# mcu_subsystem.net
KiCad netlist of a schematic drawn in Altium Designer
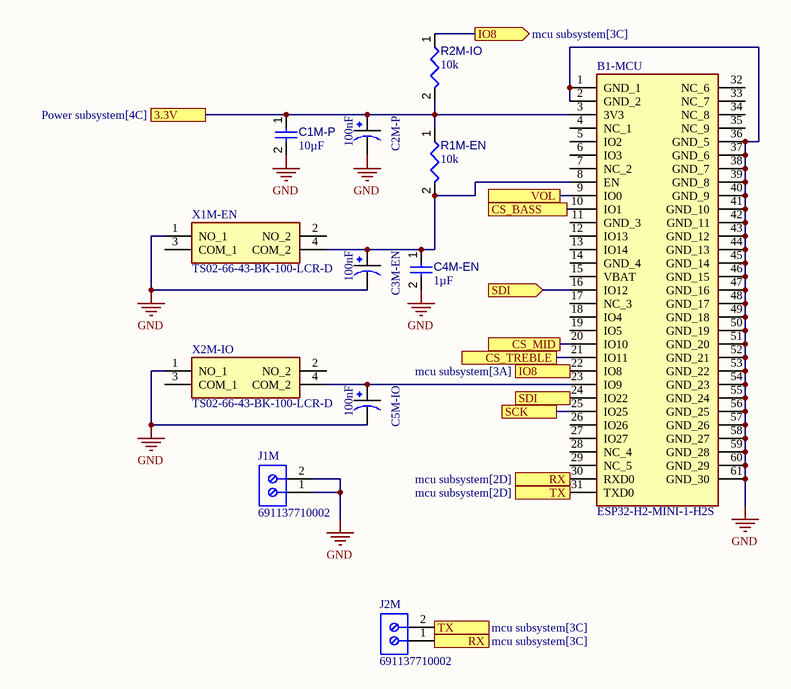
[diagram p0: mcu subsystem.SchDoc]

(export (version "E")
  (design (tool "Eeschema 10.0.6"))
  (components
    (comp (ref "B1-MCU")
      (value "ESP32-H2-MINI-1-H2S")
      (footprint "ESP32H2MINI1H2S")
      (libsource (lib "Braeden Murdock") (part "ESP32-H2-MINI-1-H2S"))
    )
    (comp (ref "C1M-P")
      (value "10µF")
      (footprint "CAPC3216X180X50NL20T25")
      (description "Chip Capacitor, 10 uF, +/- 10%, 16 V, 1206 (3216 Metric)")
      (fields (field (name "TOLERANCE") "10%") (field (name "Comment") "Capacitor 10 uF +/- 10% 16 V 1206"))
      (libsource (lib "Braeden Murdock") (part "CAP-NP-2"))
    )
    (comp (ref "C2M-P")
      (value "100nF")
      (footprint "*CAPPRD200W50D500H1100_EEUFR1E470(Primary)")
      (libsource (lib "EEUFR1E470") (part "EEUFR1E470"))
    )
    (comp (ref "C3M-EN")
      (value "100nF")
      (footprint "*CAPPRD200W50D500H1100_EEUFR1E470(Primary)")
      (libsource (lib "EEUFR1E470") (part "EEUFR1E470"))
    )
    (comp (ref "C4M-EN")
      (value "1µF")
      (footprint "CAPC3216X180X20ML20")
      (description "Chip Capacitor, 1 uF, +/- 10%, 25 V, 1206 (3216 Metric)")
      (fields (field (name "TOLERANCE") "10%") (field (name "Comment") "Capacitor 1 uF +/- 10% 25 V 1206"))
      (libsource (lib "Braeden Murdock") (part "CAP-NP-2"))
    )
    (comp (ref "C5M-IO")
      (value "100nF")
      (footprint "*CAPPRD200W50D500H1100_EEUFR1E470(Primary)")
      (libsource (lib "EEUFR1E470") (part "EEUFR1E470"))
    )
    (comp (ref "J1M")
      (value "691137710002")
      (footprint "691137710002")
      (libsource (lib "Altium Content Vault") (part "TBL - 1R - 02P - Screw"))
    )
    (comp (ref "J2M")
      (value "691137710002")
      (footprint "691137710002")
      (libsource (lib "Altium Content Vault") (part "TBL - 1R - 02P - Screw"))
    )
    (comp (ref "R1M-EN")
      (value "10k")
      (footprint "RESC3216X60X45ML15T20")
      (description "Chip Resistor, 10 KOhm, +/- 1%, 0.25 W, -55 to 155 degC, 1206 (3216 Metric)")
      (fields (field (name "TOLERANCE") "1%") (field (name "POWER") "250mW"))
      (libsource (lib "Braeden Murdock") (part "RES-2"))
    )
    (comp (ref "R2M-IO")
      (value "10k")
      (footprint "RESC3216X60X45ML15T20")
      (description "Chip Resistor, 10 KOhm, +/- 1%, 0.25 W, -55 to 155 degC, 1206 (3216 Metric)")
      (fields (field (name "TOLERANCE") "1%") (field (name "POWER") "250mW"))
      (libsource (lib "Braeden Murdock") (part "RES-2"))
    )
    (comp (ref "X1M-EN")
      (value "TS02-66-43-BK-100-LCR-D")
      (footprint "TS026643BK100LCRD")
      (fields (field (name "MOUSER PART NUMBER") "179-TS026643BK100LCR"))
      (libsource (lib "Braeden Murdock") (part "TS02-66-43-BK-100-LCR-D"))
    )
    (comp (ref "X2M-IO")
      (value "TS02-66-43-BK-100-LCR-D")
      (footprint "TS026643BK100LCRD")
      (fields (field (name "MOUSER PART NUMBER") "179-TS026643BK100LCR"))
      (libsource (lib "Braeden Murdock") (part "TS02-66-43-BK-100-LCR-D"))
    )
  )
  (nets
    (net (code "1") (name "/3.3V") (class "Default")
      (node (ref "B1-MCU") (pin "3") (pinfunction "3V3_3") (pintype "passive"))
      (node (ref "C1M-P") (pin "1") (pinfunction "1_1") (pintype "passive"))
      (node (ref "C2M-P") (pin "P") (pinfunction "P_P") (pintype "passive"))
      (node (ref "R1M-EN") (pin "1") (pinfunction "1_1") (pintype "passive"))
      (node (ref "R2M-IO") (pin "2") (pinfunction "2_2") (pintype "passive"))
    )
    (net (code "2") (name "/CS_BASS") (class "Default")
      (node (ref "B1-MCU") (pin "10") (pinfunction "IO1_10") (pintype "passive"))
    )
    (net (code "3") (name "/CS_MID") (class "Default")
      (node (ref "B1-MCU") (pin "20") (pinfunction "IO10_20") (pintype "passive"))
    )
    (net (code "4") (name "/CS_TREBLE") (class "Default")
      (node (ref "B1-MCU") (pin "21") (pinfunction "IO11_21") (pintype "passive"))
    )
    (net (code "5") (name "/IO8") (class "Default")
      (node (ref "B1-MCU") (pin "22") (pinfunction "IO8_22") (pintype "passive"))
      (node (ref "R2M-IO") (pin "1") (pinfunction "1_1") (pintype "passive"))
    )
    (net (code "6") (name "/RX") (class "Default")
      (node (ref "B1-MCU") (pin "30") (pinfunction "RXD0_30") (pintype "passive"))
      (node (ref "J2M") (pin "1") (pinfunction "1_1") (pintype "passive"))
    )
    (net (code "7") (name "/SCK") (class "Default")
      (node (ref "B1-MCU") (pin "25") (pinfunction "IO25_25") (pintype "passive"))
    )
    (net (code "8") (name "/SDI") (class "Default")
      (node (ref "B1-MCU") (pin "16") (pinfunction "IO12_16") (pintype "passive"))
      (node (ref "B1-MCU") (pin "24") (pinfunction "IO22_24") (pintype "passive"))
    )
    (net (code "9") (name "/TX") (class "Default")
      (node (ref "B1-MCU") (pin "31") (pinfunction "TXD0_31") (pintype "passive"))
      (node (ref "J2M") (pin "2") (pinfunction "2_2") (pintype "passive"))
    )
    (net (code "10") (name "/VOL") (class "Default")
      (node (ref "B1-MCU") (pin "9") (pinfunction "IO0_9") (pintype "passive"))
    )
    (net (code "11") (name "GND") (class "Default")
      (node (ref "B1-MCU") (pin "1") (pinfunction "GND_1_1") (pintype "passive"))
      (node (ref "B1-MCU") (pin "2") (pinfunction "GND_2_2") (pintype "passive"))
      (node (ref "B1-MCU") (pin "36") (pinfunction "GND_5_36") (pintype "passive"))
      (node (ref "B1-MCU") (pin "37") (pinfunction "GND_6_37") (pintype "passive"))
      (node (ref "B1-MCU") (pin "38") (pinfunction "GND_7_38") (pintype "passive"))
      (node (ref "B1-MCU") (pin "39") (pinfunction "GND_8_39") (pintype "passive"))
      (node (ref "B1-MCU") (pin "40") (pinfunction "GND_9_40") (pintype "passive"))
      (node (ref "B1-MCU") (pin "41") (pinfunction "GND_10_41") (pintype "passive"))
      (node (ref "B1-MCU") (pin "42") (pinfunction "GND_11_42") (pintype "passive"))
      (node (ref "B1-MCU") (pin "43") (pinfunction "GND_12_43") (pintype "passive"))
      (node (ref "B1-MCU") (pin "44") (pinfunction "GND_13_44") (pintype "passive"))
      (node (ref "B1-MCU") (pin "45") (pinfunction "GND_14_45") (pintype "passive"))
      (node (ref "B1-MCU") (pin "46") (pinfunction "GND_15_46") (pintype "passive"))
      (node (ref "B1-MCU") (pin "47") (pinfunction "GND_16_47") (pintype "passive"))
      (node (ref "B1-MCU") (pin "48") (pinfunction "GND_17_48") (pintype "passive"))
      (node (ref "B1-MCU") (pin "49") (pinfunction "GND_18_49") (pintype "passive"))
      (node (ref "B1-MCU") (pin "50") (pinfunction "GND_19_50") (pintype "passive"))
      (node (ref "B1-MCU") (pin "51") (pinfunction "GND_20_51") (pintype "passive"))
      (node (ref "B1-MCU") (pin "52") (pinfunction "GND_21_52") (pintype "passive"))
      (node (ref "B1-MCU") (pin "53") (pinfunction "GND_22_53") (pintype "passive"))
      (node (ref "B1-MCU") (pin "54") (pinfunction "GND_23_54") (pintype "passive"))
      (node (ref "B1-MCU") (pin "55") (pinfunction "GND_24_55") (pintype "passive"))
      (node (ref "B1-MCU") (pin "56") (pinfunction "GND_25_56") (pintype "passive"))
      (node (ref "B1-MCU") (pin "57") (pinfunction "GND_26_57") (pintype "passive"))
      (node (ref "B1-MCU") (pin "58") (pinfunction "GND_27_58") (pintype "passive"))
      (node (ref "B1-MCU") (pin "59") (pinfunction "GND_28_59") (pintype "passive"))
      (node (ref "B1-MCU") (pin "60") (pinfunction "GND_29_60") (pintype "passive"))
      (node (ref "B1-MCU") (pin "61") (pinfunction "GND_30_61") (pintype "passive"))
      (node (ref "C1M-P") (pin "2") (pinfunction "2_2") (pintype "passive"))
      (node (ref "C2M-P") (pin "N") (pinfunction "N_N") (pintype "passive"))
      (node (ref "C3M-EN") (pin "N") (pinfunction "N_N") (pintype "passive"))
      (node (ref "C4M-EN") (pin "2") (pinfunction "2_2") (pintype "passive"))
      (node (ref "C5M-IO") (pin "N") (pinfunction "N_N") (pintype "passive"))
      (node (ref "J1M") (pin "1") (pinfunction "1_1") (pintype "passive"))
      (node (ref "J1M") (pin "2") (pinfunction "2_2") (pintype "passive"))
      (node (ref "X1M-EN") (pin "1") (pinfunction "NO_1_1") (pintype "passive"))
      (node (ref "X2M-IO") (pin "1") (pinfunction "NO_1_1") (pintype "passive"))
    )
    (net (code "12") (name "Net-(B1-MCU-EN)") (class "Default")
      (node (ref "B1-MCU") (pin "8") (pinfunction "EN_8") (pintype "passive"))
      (node (ref "C3M-EN") (pin "P") (pinfunction "P_P") (pintype "passive"))
      (node (ref "C4M-EN") (pin "1") (pinfunction "1_1") (pintype "passive"))
      (node (ref "R1M-EN") (pin "2") (pinfunction "2_2") (pintype "passive"))
      (node (ref "X1M-EN") (pin "4") (pinfunction "COM_2_4") (pintype "passive"))
    )
    (net (code "13") (name "Net-(B1-MCU-IO9)") (class "Default")
      (node (ref "B1-MCU") (pin "23") (pinfunction "IO9_23") (pintype "passive"))
      (node (ref "C5M-IO") (pin "P") (pinfunction "P_P") (pintype "passive"))
      (node (ref "X2M-IO") (pin "4") (pinfunction "COM_2_4") (pintype "passive"))
    )
    (net (code "14") (name "unconnected-(B1-MCU-GND_3-Pad11)") (class "Default")
      (node (ref "B1-MCU") (pin "11") (pinfunction "GND_3_11") (pintype "passive"))
    )
    (net (code "15") (name "unconnected-(B1-MCU-GND_4-Pad14)") (class "Default")
      (node (ref "B1-MCU") (pin "14") (pinfunction "GND_4_14") (pintype "passive"))
    )
    (net (code "16") (name "unconnected-(B1-MCU-IO2-Pad5)") (class "Default")
      (node (ref "B1-MCU") (pin "5") (pinfunction "IO2_5") (pintype "passive"))
    )
    (net (code "17") (name "unconnected-(B1-MCU-IO3-Pad6)") (class "Default")
      (node (ref "B1-MCU") (pin "6") (pinfunction "IO3_6") (pintype "passive"))
    )
    (net (code "18") (name "unconnected-(B1-MCU-IO4-Pad18)") (class "Default")
      (node (ref "B1-MCU") (pin "18") (pinfunction "IO4_18") (pintype "passive"))
    )
    (net (code "19") (name "unconnected-(B1-MCU-IO5-Pad19)") (class "Default")
      (node (ref "B1-MCU") (pin "19") (pinfunction "IO5_19") (pintype "passive"))
    )
    (net (code "20") (name "unconnected-(B1-MCU-IO13-Pad12)") (class "Default")
      (node (ref "B1-MCU") (pin "12") (pinfunction "IO13_12") (pintype "passive"))
    )
    (net (code "21") (name "unconnected-(B1-MCU-IO14-Pad13)") (class "Default")
      (node (ref "B1-MCU") (pin "13") (pinfunction "IO14_13") (pintype "passive"))
    )
    (net (code "22") (name "unconnected-(B1-MCU-IO26-Pad26)") (class "Default")
      (node (ref "B1-MCU") (pin "26") (pinfunction "IO26_26") (pintype "passive"))
    )
    (net (code "23") (name "unconnected-(B1-MCU-IO27-Pad27)") (class "Default")
      (node (ref "B1-MCU") (pin "27") (pinfunction "IO27_27") (pintype "passive"))
    )
    (net (code "24") (name "unconnected-(B1-MCU-NC_1-Pad4)") (class "Default")
      (node (ref "B1-MCU") (pin "4") (pinfunction "NC_1_4") (pintype "passive"))
    )
    (net (code "25") (name "unconnected-(B1-MCU-NC_2-Pad7)") (class "Default")
      (node (ref "B1-MCU") (pin "7") (pinfunction "NC_2_7") (pintype "passive"))
    )
    (net (code "26") (name "unconnected-(B1-MCU-NC_3-Pad17)") (class "Default")
      (node (ref "B1-MCU") (pin "17") (pinfunction "NC_3_17") (pintype "passive"))
    )
    (net (code "27") (name "unconnected-(B1-MCU-NC_4-Pad28)") (class "Default")
      (node (ref "B1-MCU") (pin "28") (pinfunction "NC_4_28") (pintype "passive"))
    )
    (net (code "28") (name "unconnected-(B1-MCU-NC_5-Pad29)") (class "Default")
      (node (ref "B1-MCU") (pin "29") (pinfunction "NC_5_29") (pintype "passive"))
    )
    (net (code "29") (name "unconnected-(B1-MCU-NC_6-Pad32)") (class "Default")
      (node (ref "B1-MCU") (pin "32") (pinfunction "NC_6_32") (pintype "passive"))
    )
    (net (code "30") (name "unconnected-(B1-MCU-NC_7-Pad33)") (class "Default")
      (node (ref "B1-MCU") (pin "33") (pinfunction "NC_7_33") (pintype "passive"))
    )
    (net (code "31") (name "unconnected-(B1-MCU-NC_8-Pad34)") (class "Default")
      (node (ref "B1-MCU") (pin "34") (pinfunction "NC_8_34") (pintype "passive"))
    )
    (net (code "32") (name "unconnected-(B1-MCU-NC_9-Pad35)") (class "Default")
      (node (ref "B1-MCU") (pin "35") (pinfunction "NC_9_35") (pintype "passive"))
    )
    (net (code "33") (name "unconnected-(B1-MCU-VBAT-Pad15)") (class "Default")
      (node (ref "B1-MCU") (pin "15") (pinfunction "VBAT_15") (pintype "passive"))
    )
    (net (code "34") (name "unconnected-(X1M-EN-COM_1-Pad3)") (class "Default")
      (node (ref "X1M-EN") (pin "3") (pinfunction "COM_1_3") (pintype "passive"))
    )
    (net (code "35") (name "unconnected-(X1M-EN-NO_2-Pad2)") (class "Default")
      (node (ref "X1M-EN") (pin "2") (pinfunction "NO_2_2") (pintype "passive"))
    )
    (net (code "36") (name "unconnected-(X2M-IO-COM_1-Pad3)") (class "Default")
      (node (ref "X2M-IO") (pin "3") (pinfunction "COM_1_3") (pintype "passive"))
    )
    (net (code "37") (name "unconnected-(X2M-IO-NO_2-Pad2)") (class "Default")
      (node (ref "X2M-IO") (pin "2") (pinfunction "NO_2_2") (pintype "passive"))
    )
  )
)
